# PcbAssignment.net
KiCad netlist of a schematic drawn in Altium Designer
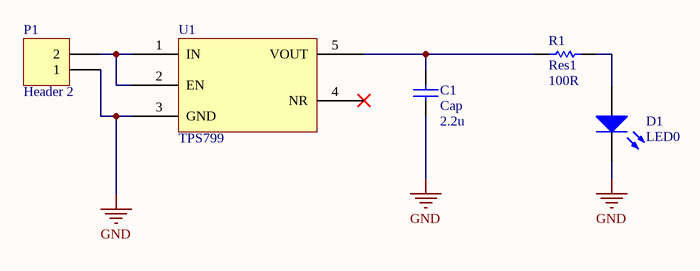
[diagram p0: PcbAssignment.SchDoc]

(export (version "E")
  (design (tool "Eeschema 10.0.6"))
  (components
    (comp (ref "C1")
      (value "Cap")
      (footprint "RAD-0.3")
      (description "Capacitor")
      (fields (field (name "ALTIUM_VALUE") "2.2u") (field (name "PUBLISHER") "Altium Limited"))
      (libsource (lib "Miscellaneous Devices") (part "Cap"))
    )
    (comp (ref "D1")
      (value "LED0")
      (footprint "LED-0")
      (description "Typical INFRARED GaAs LED")
      (fields (field (name "PUBLISHER") "Altium Limited"))
      (libsource (lib "Miscellaneous Devices") (part "LED0"))
    )
    (comp (ref "P1")
      (value "Header 2")
      (footprint "HDR1X2")
      (description "Header, 2-Pin")
      (fields (field (name "PUBLISHER") "Altium Limited"))
      (libsource (lib "Miscellaneous Connectors") (part "Header 2"))
    )
    (comp (ref "R1")
      (value "Res1")
      (footprint "AXIAL-0.3")
      (description "Resistor")
      (fields (field (name "ALTIUM_VALUE") "100R") (field (name "PUBLISHER") "Altium Limited"))
      (libsource (lib "Miscellaneous Devices") (part "Res1"))
    )
    (comp (ref "U1")
      (value "TPS799")
      (footprint "SOT-5")
      (libsource (lib "PcbAssignmentLib") (part "TPS799"))
    )
  )
  (nets
    (net (code "1") (name "GND") (class "Default")
      (node (ref "C1") (pin "1") (pinfunction "1_1") (pintype "passive"))
      (node (ref "D1") (pin "2") (pinfunction "K_2") (pintype "passive"))
      (node (ref "P1") (pin "1") (pinfunction "1_1") (pintype "passive"))
      (node (ref "U1") (pin "3") (pinfunction "GND_3") (pintype "passive"))
    )
    (net (code "2") (name "Net-(D1-A)") (class "Default")
      (node (ref "D1") (pin "1") (pinfunction "A_1") (pintype "passive"))
      (node (ref "R1") (pin "1") (pinfunction "1_1") (pintype "passive"))
    )
    (net (code "3") (name "Net-(U1-EN)") (class "Default")
      (node (ref "P1") (pin "2") (pinfunction "2_2") (pintype "passive"))
      (node (ref "U1") (pin "1") (pinfunction "IN_1") (pintype "passive"))
      (node (ref "U1") (pin "2") (pinfunction "EN_2") (pintype "passive"))
    )
    (net (code "4") (name "Net-(U1-VOUT)") (class "Default")
      (node (ref "C1") (pin "2") (pinfunction "2_2") (pintype "passive"))
      (node (ref "R1") (pin "2") (pinfunction "2_2") (pintype "passive"))
      (node (ref "U1") (pin "5") (pinfunction "VOUT_5") (pintype "passive"))
    )
    (net (code "5") (name "unconnected-(U1-NR-Pad4)") (class "Default")
      (node (ref "U1") (pin "4") (pinfunction "NR_4") (pintype "passive+no_connect"))
    )
  )
)
